# gsm.net
KiCad netlist of a schematic drawn in Altium Designer
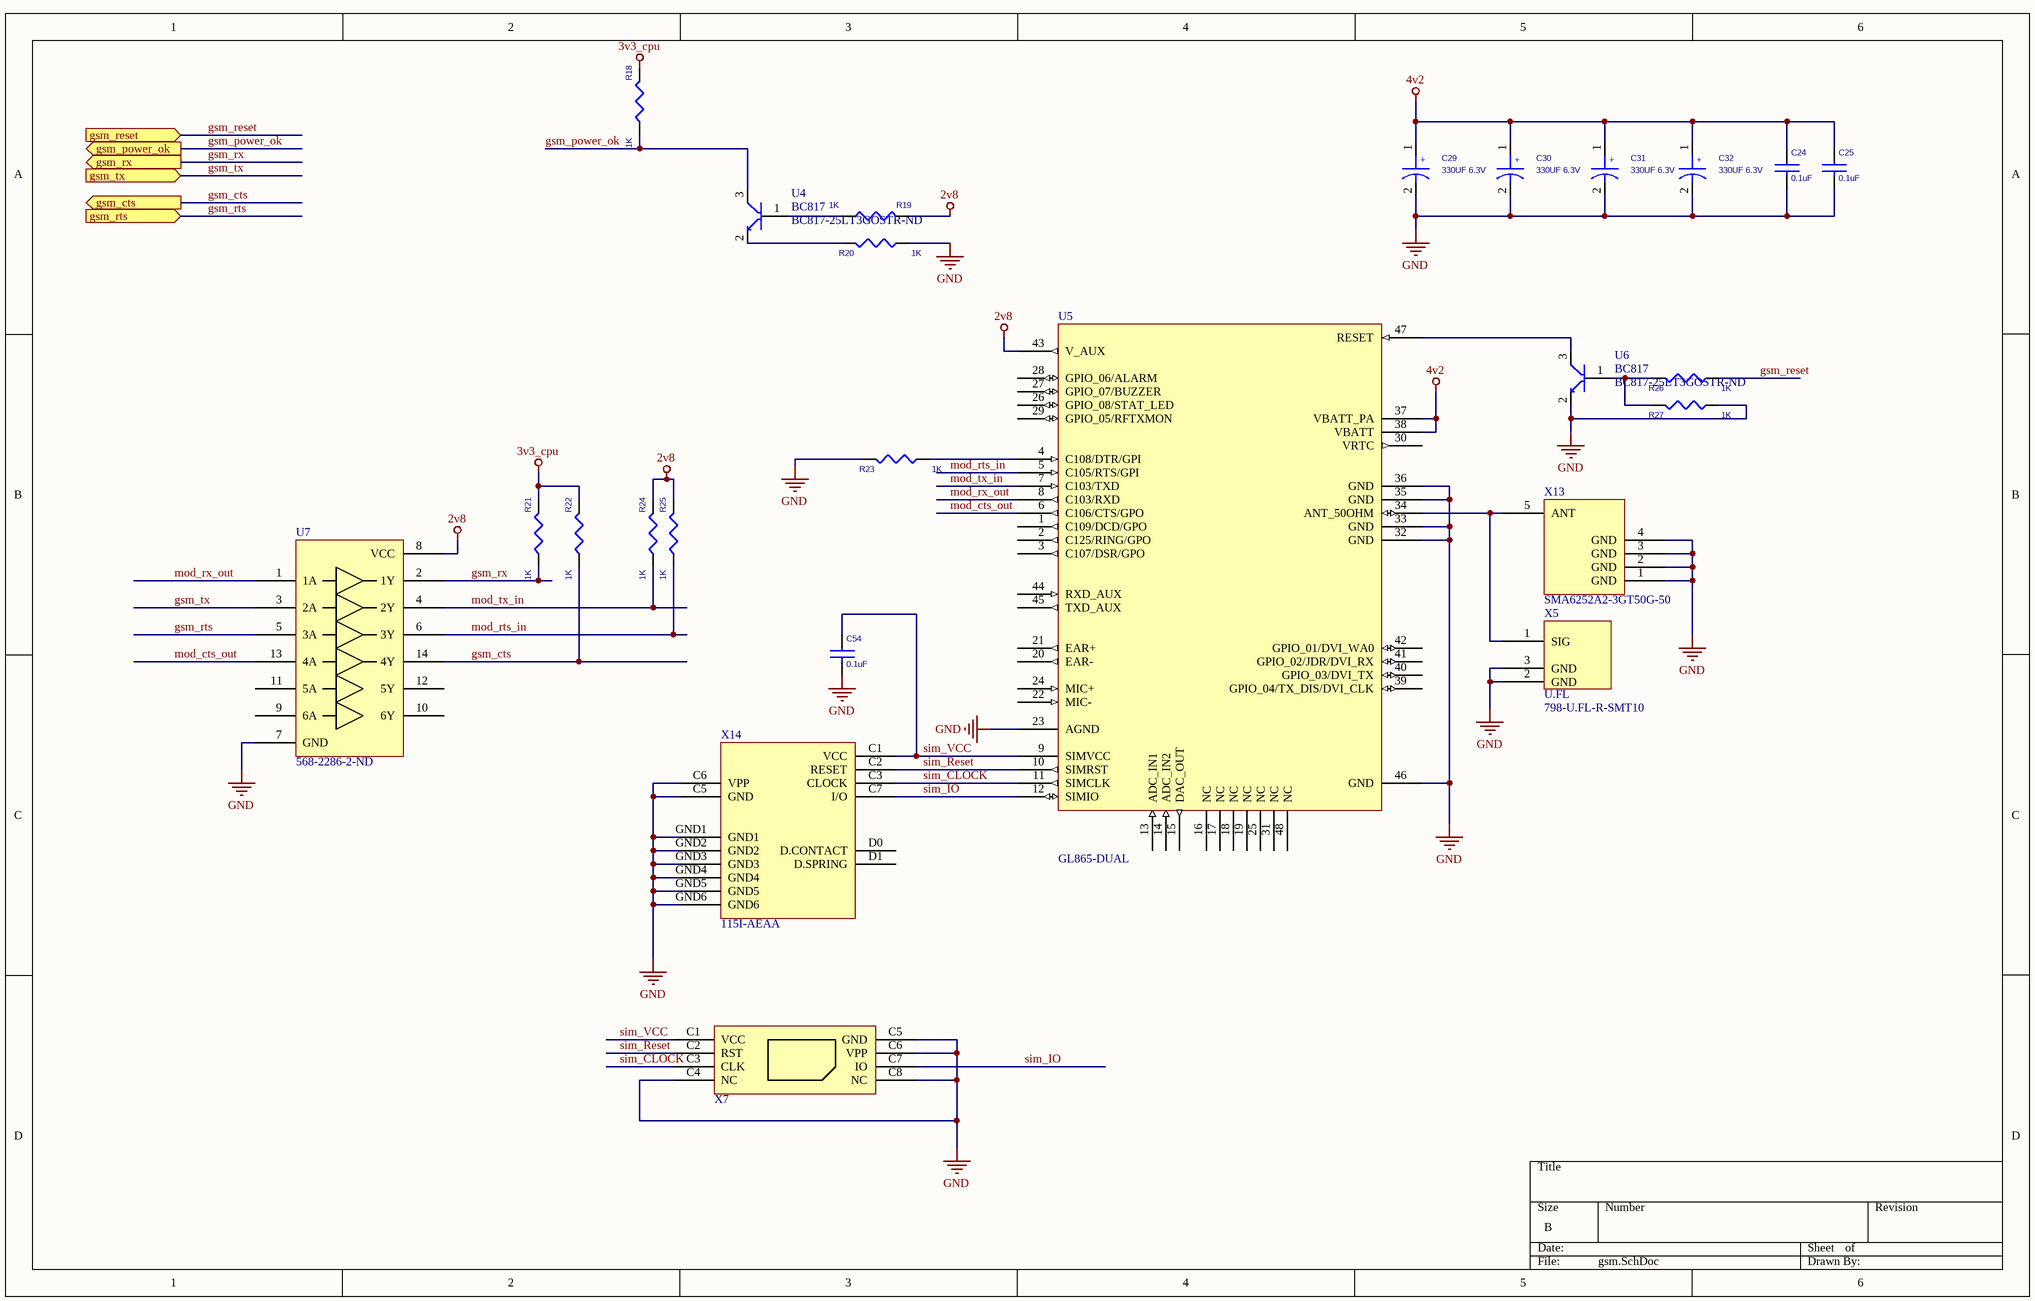
[diagram p0: gsm.SchDoc]

(export (version "E")
  (design (tool "Eeschema 10.0.6"))
  (components
    (comp (ref "C24")
      (value "0.1uF")
      (footprint "CAPC2012X09M")
      (description "CAP CER 0.1UF 25V 10% X7R 0805")
      (libsource (lib "Capacitors") (part "CAP_SMD_0.1UF_10%"))
    )
    (comp (ref "C25")
      (value "0.1uF")
      (footprint "CAPC2012X09M")
      (description "CAP CER 0.1UF 25V 10% X7R 0805")
      (libsource (lib "Capacitors") (part "CAP_SMD_0.1UF_10%"))
    )
    (comp (ref "C29")
      (value "330UF 6.3V")
      (footprint "CAPMP7143X31N")
      (description "CAP 330uF; 6.3V; Case: D")
      (libsource (lib "Capacitors") (part "CAP_SMD_330UF_10%"))
    )
    (comp (ref "C30")
      (value "330UF 6.3V")
      (footprint "CAPMP7143X31N")
      (description "CAP 330uF; 6.3V; Case: D")
      (libsource (lib "Capacitors") (part "CAP_SMD_330UF_10%"))
    )
    (comp (ref "C31")
      (value "330UF 6.3V")
      (footprint "CAPMP7143X31N")
      (description "CAP 330uF; 6.3V; Case: D")
      (libsource (lib "Capacitors") (part "CAP_SMD_330UF_10%"))
    )
    (comp (ref "C32")
      (value "330UF 6.3V")
      (footprint "CAPMP7143X31N")
      (description "CAP 330uF; 6.3V; Case: D")
      (libsource (lib "Capacitors") (part "CAP_SMD_330UF_10%"))
    )
    (comp (ref "C54")
      (value "0.1uF")
      (footprint "CAPC2012X09M")
      (description "CAP CER 0.1UF 25V 10% X7R 0805")
      (libsource (lib "Capacitors") (part "CAP_SMD_0.1UF_10%"))
    )
    (comp (ref "R18")
      (value "1K")
      (footprint "RESC2013X06M")
      (description "RES - 1K OHM, 5%, 1/8W, 0805 SMD")
      (libsource (lib "Resistors") (part "RES_SMD_1K_5%"))
    )
    (comp (ref "R19")
      (value "1K")
      (footprint "RESC2013X06M")
      (description "RES - 1K OHM, 5%, 1/8W, 0805 SMD")
      (libsource (lib "Resistors") (part "RES_SMD_1K_5%"))
    )
    (comp (ref "R20")
      (value "1K")
      (footprint "RESC2013X06M")
      (description "RES - 1K OHM, 5%, 1/8W, 0805 SMD")
      (libsource (lib "Resistors") (part "RES_SMD_1K_5%"))
    )
    (comp (ref "R21")
      (value "1K")
      (footprint "RESC2013X06M")
      (description "RES - 1K OHM, 5%, 1/8W, 0805 SMD")
      (libsource (lib "Resistors") (part "RES_SMD_1K_5%"))
    )
    (comp (ref "R22")
      (value "1K")
      (footprint "RESC2013X06M")
      (description "RES - 1K OHM, 5%, 1/8W, 0805 SMD")
      (libsource (lib "Resistors") (part "RES_SMD_1K_5%"))
    )
    (comp (ref "R23")
      (value "1K")
      (footprint "RESC2013X06M")
      (description "RES - 1K OHM, 5%, 1/8W, 0805 SMD")
      (libsource (lib "Resistors") (part "RES_SMD_1K_5%"))
    )
    (comp (ref "R24")
      (value "1K")
      (footprint "RESC2013X06M")
      (description "RES - 1K OHM, 5%, 1/8W, 0805 SMD")
      (libsource (lib "Resistors") (part "RES_SMD_1K_5%"))
    )
    (comp (ref "R25")
      (value "1K")
      (footprint "RESC2013X06M")
      (description "RES - 1K OHM, 5%, 1/8W, 0805 SMD")
      (libsource (lib "Resistors") (part "RES_SMD_1K_5%"))
    )
    (comp (ref "R26")
      (value "1K")
      (footprint "RESC2013X06M")
      (description "RES - 1K OHM, 5%, 1/8W, 0805 SMD")
      (libsource (lib "Resistors") (part "RES_SMD_1K_5%"))
    )
    (comp (ref "R27")
      (value "1K")
      (footprint "RESC2013X06M")
      (description "RES - 1K OHM, 5%, 1/8W, 0805 SMD")
      (libsource (lib "Resistors") (part "RES_SMD_1K_5%"))
    )
    (comp (ref "U4")
      (value "BC817")
      (footprint "SOT95P237X111-3N_SOT-23")
      (fields (field (name "SUPPLIER PART NUMBER 1") "BC817-25LT3GOSTR-ND"))
      (libsource (lib "TruthEar") (part "BC817"))
    )
    (comp (ref "U5")
      (value "GL865-DUAL")
      (footprint "GL865_FOOT")
      (libsource (lib "TruthEar") (part "GL865-DUAL"))
    )
    (comp (ref "U6")
      (value "BC817")
      (footprint "SOT95P237X111-3N_SOT-23")
      (fields (field (name "SUPPLIER PART NUMBER 1") "BC817-25LT3GOSTR-ND"))
      (libsource (lib "TruthEar") (part "BC817"))
    )
    (comp (ref "U7")
      (value "74LVC07A")
      (footprint "TSOP127P600X145-14N")
      (fields (field (name "SUPPLIER PART NUMBER 1") "568-2286-2-ND"))
      (libsource (lib "TruthEar") (part "74LVC07A"))
    )
    (comp (ref "X5")
      (value "U.FL")
      (footprint "U.FL")
      (fields (field (name "SUPPLIER PART NUMBER 1") "798-U.FL-R-SMT10"))
      (libsource (lib "Connectors") (part "U.FL"))
    )
    (comp (ref "X7")
      (value "MOLEX")
      (footprint "MOLEX-91228-001")
      (libsource (lib "Connectors") (part "MOLEX_SIM"))
    )
    (comp (ref "X13")
      (value "SMA6252A2-3GT50G-50")
      (footprint "SMA6252A2-3GT50G-50")
      (libsource (lib "Connectors") (part "SMA_CONN"))
    )
    (comp (ref "X14")
      (value "115I-AEAA")
      (footprint "115I-AEAA")
      (libsource (lib "Connectors") (part "SIM_CARD_115I-AEAA"))
    )
  )
  (nets
    (net (code "1") (name "/gsm_cts") (class "Default")
      (node (ref "R22") (pin "1") (pinfunction "1_1") (pintype "passive"))
      (node (ref "U7") (pin "14") (pinfunction "4Y_14") (pintype "power_in"))
    )
    (net (code "2") (name "/gsm_power_ok") (class "Default")
      (node (ref "R18") (pin "1") (pinfunction "1_1") (pintype "passive"))
      (node (ref "U4") (pin "3") (pinfunction "C_3") (pintype "passive"))
    )
    (net (code "3") (name "/gsm_reset") (class "Default")
      (node (ref "R26") (pin "1") (pinfunction "1_1") (pintype "passive"))
    )
    (net (code "4") (name "/gsm_rts") (class "Default")
      (node (ref "U7") (pin "5") (pinfunction "3A_5") (pintype "power_in"))
    )
    (net (code "5") (name "/gsm_rx") (class "Default")
      (node (ref "R21") (pin "1") (pinfunction "1_1") (pintype "passive"))
      (node (ref "U7") (pin "2") (pinfunction "1Y_2") (pintype "power_in"))
    )
    (net (code "6") (name "/gsm_tx") (class "Default")
      (node (ref "U7") (pin "3") (pinfunction "2A_3") (pintype "power_in"))
    )
    (net (code "7") (name "/mod_cts_out") (class "Default")
      (node (ref "U5") (pin "6") (pinfunction "C106/CTS/GPO_6") (pintype "output"))
      (node (ref "U7") (pin "13") (pinfunction "4A_13") (pintype "power_in"))
    )
    (net (code "8") (name "/mod_rts_in") (class "Default")
      (node (ref "R25") (pin "1") (pinfunction "1_1") (pintype "passive"))
      (node (ref "U5") (pin "5") (pinfunction "C105/RTS/GPI_5") (pintype "input"))
      (node (ref "U7") (pin "6") (pinfunction "3Y_6") (pintype "power_in"))
    )
    (net (code "9") (name "/mod_rx_out") (class "Default")
      (node (ref "U5") (pin "8") (pinfunction "C103/RXD_8") (pintype "output"))
      (node (ref "U7") (pin "1") (pinfunction "1A_1") (pintype "power_in"))
    )
    (net (code "10") (name "/mod_tx_in") (class "Default")
      (node (ref "R24") (pin "1") (pinfunction "1_1") (pintype "passive"))
      (node (ref "U5") (pin "7") (pinfunction "C103/TXD_7") (pintype "input"))
      (node (ref "U7") (pin "4") (pinfunction "2Y_4") (pintype "power_in"))
    )
    (net (code "11") (name "/sim_CLOCK") (class "Default")
      (node (ref "U5") (pin "11") (pinfunction "SIMCLK_11") (pintype "output"))
      (node (ref "X14") (pin "C3") (pinfunction "CLOCK_C3") (pintype "passive"))
      (node (ref "X7") (pin "C3") (pinfunction "CLK_C3") (pintype "power_in"))
    )
    (net (code "12") (name "/sim_IO") (class "Default")
      (node (ref "U5") (pin "12") (pinfunction "SIMIO_12") (pintype "bidirectional"))
      (node (ref "X14") (pin "C7") (pinfunction "I/O_C7") (pintype "passive"))
      (node (ref "X7") (pin "C7") (pinfunction "IO_C7") (pintype "power_in"))
    )
    (net (code "13") (name "/sim_Reset") (class "Default")
      (node (ref "U5") (pin "10") (pinfunction "SIMRST_10") (pintype "output"))
      (node (ref "X14") (pin "C2") (pinfunction "RESET_C2") (pintype "passive"))
      (node (ref "X7") (pin "C2") (pinfunction "RST_C2") (pintype "power_in"))
    )
    (net (code "14") (name "/sim_VCC") (class "Default")
      (node (ref "C54") (pin "1") (pinfunction "1_1") (pintype "passive"))
      (node (ref "U5") (pin "9") (pinfunction "SIMVCC_9") (pintype "passive"))
      (node (ref "X14") (pin "C1") (pinfunction "VCC_C1") (pintype "passive"))
      (node (ref "X7") (pin "C1") (pinfunction "VCC_C1") (pintype "power_in"))
    )
    (net (code "15") (name "2v8") (class "Default")
      (node (ref "R19") (pin "2") (pinfunction "2_2") (pintype "passive"))
      (node (ref "R24") (pin "2") (pinfunction "2_2") (pintype "passive"))
      (node (ref "R25") (pin "2") (pinfunction "2_2") (pintype "passive"))
      (node (ref "U5") (pin "43") (pinfunction "V_AUX_43") (pintype "output"))
      (node (ref "U7") (pin "8") (pinfunction "VCC_8") (pintype "power_in"))
    )
    (net (code "16") (name "3v3_cpu") (class "Default")
      (node (ref "R18") (pin "2") (pinfunction "2_2") (pintype "passive"))
      (node (ref "R21") (pin "2") (pinfunction "2_2") (pintype "passive"))
      (node (ref "R22") (pin "2") (pinfunction "2_2") (pintype "passive"))
    )
    (net (code "17") (name "4v2") (class "Default")
      (node (ref "C24") (pin "1") (pinfunction "1_1") (pintype "passive"))
      (node (ref "C25") (pin "1") (pinfunction "1_1") (pintype "passive"))
      (node (ref "C29") (pin "1") (pinfunction "1_1") (pintype "passive"))
      (node (ref "C30") (pin "1") (pinfunction "1_1") (pintype "passive"))
      (node (ref "C31") (pin "1") (pinfunction "1_1") (pintype "passive"))
      (node (ref "C32") (pin "1") (pinfunction "1_1") (pintype "passive"))
      (node (ref "U5") (pin "37") (pinfunction "VBATT_PA_37") (pintype "passive"))
      (node (ref "U5") (pin "38") (pinfunction "VBATT_38") (pintype "passive"))
    )
    (net (code "18") (name "GND") (class "Default")
      (node (ref "C24") (pin "2") (pinfunction "2_2") (pintype "passive"))
      (node (ref "C25") (pin "2") (pinfunction "2_2") (pintype "passive"))
      (node (ref "C29") (pin "2") (pinfunction "2_2") (pintype "passive"))
      (node (ref "C30") (pin "2") (pinfunction "2_2") (pintype "passive"))
      (node (ref "C31") (pin "2") (pinfunction "2_2") (pintype "passive"))
      (node (ref "C32") (pin "2") (pinfunction "2_2") (pintype "passive"))
      (node (ref "C54") (pin "2") (pinfunction "2_2") (pintype "passive"))
      (node (ref "R20") (pin "1") (pinfunction "1_1") (pintype "passive"))
      (node (ref "R23") (pin "2") (pinfunction "2_2") (pintype "passive"))
      (node (ref "R27") (pin "1") (pinfunction "1_1") (pintype "passive"))
      (node (ref "U5") (pin "23") (pinfunction "AGND_23") (pintype "passive"))
      (node (ref "U5") (pin "32") (pinfunction "GND_32") (pintype "passive"))
      (node (ref "U5") (pin "33") (pinfunction "GND_33") (pintype "passive"))
      (node (ref "U5") (pin "35") (pinfunction "GND_35") (pintype "passive"))
      (node (ref "U5") (pin "36") (pinfunction "GND_36") (pintype "passive"))
      (node (ref "U5") (pin "46") (pinfunction "GND_46") (pintype "passive"))
      (node (ref "U6") (pin "2") (pinfunction "E_2") (pintype "passive"))
      (node (ref "U7") (pin "7") (pinfunction "GND_7") (pintype "power_in"))
      (node (ref "X13") (pin "1") (pinfunction "GND_1") (pintype "passive"))
      (node (ref "X13") (pin "2") (pinfunction "GND_2") (pintype "passive"))
      (node (ref "X13") (pin "3") (pinfunction "GND_3") (pintype "passive"))
      (node (ref "X13") (pin "4") (pinfunction "GND_4") (pintype "passive"))
      (node (ref "X14") (pin "C5") (pinfunction "GND_C5") (pintype "passive"))
      (node (ref "X14") (pin "C6") (pinfunction "VPP_C6") (pintype "passive"))
      (node (ref "X14") (pin "GND1") (pinfunction "GND1_GND1") (pintype "passive"))
      (node (ref "X14") (pin "GND2") (pinfunction "GND2_GND2") (pintype "passive"))
      (node (ref "X14") (pin "GND3") (pinfunction "GND3_GND3") (pintype "passive"))
      (node (ref "X14") (pin "GND4") (pinfunction "GND4_GND4") (pintype "passive"))
      (node (ref "X14") (pin "GND5") (pinfunction "GND5_GND5") (pintype "passive"))
      (node (ref "X14") (pin "GND6") (pinfunction "GND6_GND6") (pintype "passive"))
      (node (ref "X5") (pin "2") (pinfunction "GND_2") (pintype "passive"))
      (node (ref "X5") (pin "3") (pinfunction "GND_3") (pintype "passive"))
      (node (ref "X7") (pin "C4") (pinfunction "NC_C4") (pintype "power_in"))
      (node (ref "X7") (pin "C5") (pinfunction "GND_C5") (pintype "power_in"))
      (node (ref "X7") (pin "C6") (pinfunction "VPP_C6") (pintype "power_in"))
      (node (ref "X7") (pin "C8") (pinfunction "NC_C8") (pintype "power_in"))
    )
    (net (code "19") (name "Net-(U4-B)") (class "Default")
      (node (ref "R19") (pin "1") (pinfunction "1_1") (pintype "passive"))
      (node (ref "U4") (pin "1") (pinfunction "B_1") (pintype "passive"))
    )
    (net (code "20") (name "Net-(U4-E)") (class "Default")
      (node (ref "R20") (pin "2") (pinfunction "2_2") (pintype "passive"))
      (node (ref "U4") (pin "2") (pinfunction "E_2") (pintype "passive"))
    )
    (net (code "21") (name "Net-(U5-ANT_50OHM)") (class "Default")
      (node (ref "U5") (pin "34") (pinfunction "ANT_50OHM_34") (pintype "bidirectional"))
      (node (ref "X13") (pin "5") (pinfunction "ANT_5") (pintype "passive"))
      (node (ref "X5") (pin "1") (pinfunction "SIG_1") (pintype "passive"))
    )
    (net (code "22") (name "Net-(U5-C108{slash}DTR{slash}GPI)") (class "Default")
      (node (ref "R23") (pin "1") (pinfunction "1_1") (pintype "passive"))
      (node (ref "U5") (pin "4") (pinfunction "C108/DTR/GPI_4") (pintype "input"))
    )
    (net (code "23") (name "Net-(U5-RESET)") (class "Default")
      (node (ref "U5") (pin "47") (pinfunction "RESET_47") (pintype "input"))
      (node (ref "U6") (pin "3") (pinfunction "C_3") (pintype "passive"))
    )
    (net (code "24") (name "Net-(U6-B)") (class "Default")
      (node (ref "R26") (pin "2") (pinfunction "2_2") (pintype "passive"))
      (node (ref "R27") (pin "2") (pinfunction "2_2") (pintype "passive"))
      (node (ref "U6") (pin "1") (pinfunction "B_1") (pintype "passive"))
    )
    (net (code "25") (name "unconnected-(U5-ADC_IN1-Pad13)") (class "Default")
      (node (ref "U5") (pin "13") (pinfunction "ADC_IN1_13") (pintype "input"))
    )
    (net (code "26") (name "unconnected-(U5-ADC_IN2-Pad14)") (class "Default")
      (node (ref "U5") (pin "14") (pinfunction "ADC_IN2_14") (pintype "input"))
    )
    (net (code "27") (name "unconnected-(U5-C107{slash}DSR{slash}GPO-Pad3)") (class "Default")
      (node (ref "U5") (pin "3") (pinfunction "C107/DSR/GPO_3") (pintype "output"))
    )
    (net (code "28") (name "unconnected-(U5-C109{slash}DCD{slash}GPO-Pad1)") (class "Default")
      (node (ref "U5") (pin "1") (pinfunction "C109/DCD/GPO_1") (pintype "output"))
    )
    (net (code "29") (name "unconnected-(U5-C125{slash}RING{slash}GPO-Pad2)") (class "Default")
      (node (ref "U5") (pin "2") (pinfunction "C125/RING/GPO_2") (pintype "output"))
    )
    (net (code "30") (name "unconnected-(U5-DAC_OUT-Pad15)") (class "Default")
      (node (ref "U5") (pin "15") (pinfunction "DAC_OUT_15") (pintype "output"))
    )
    (net (code "31") (name "unconnected-(U5-EAR+-Pad21)") (class "Default")
      (node (ref "U5") (pin "21") (pinfunction "EAR+_21") (pintype "output"))
    )
    (net (code "32") (name "unconnected-(U5-EAR--Pad20)") (class "Default")
      (node (ref "U5") (pin "20") (pinfunction "EAR-_20") (pintype "output"))
    )
    (net (code "33") (name "unconnected-(U5-GPIO_01{slash}DVI_WA0-Pad42)") (class "Default")
      (node (ref "U5") (pin "42") (pinfunction "GPIO_01/DVI_WA0_42") (pintype "bidirectional"))
    )
    (net (code "34") (name "unconnected-(U5-GPIO_02{slash}JDR{slash}DVI_RX-Pad41)") (class "Default")
      (node (ref "U5") (pin "41") (pinfunction "GPIO_02/JDR/DVI_RX_41") (pintype "bidirectional"))
    )
    (net (code "35") (name "unconnected-(U5-GPIO_03{slash}DVI_TX-Pad40)") (class "Default")
      (node (ref "U5") (pin "40") (pinfunction "GPIO_03/DVI_TX_40") (pintype "bidirectional"))
    )
    (net (code "36") (name "unconnected-(U5-GPIO_04{slash}TX_DIS{slash}DVI_CLK-Pad39)") (class "Default")
      (node (ref "U5") (pin "39") (pinfunction "GPIO_04/TX_DIS/DVI_CLK_39") (pintype "bidirectional"))
    )
    (net (code "37") (name "unconnected-(U5-GPIO_05{slash}RFTXMON-Pad29)") (class "Default")
      (node (ref "U5") (pin "29") (pinfunction "GPIO_05/RFTXMON_29") (pintype "bidirectional"))
    )
    (net (code "38") (name "unconnected-(U5-GPIO_06{slash}ALARM-Pad28)") (class "Default")
      (node (ref "U5") (pin "28") (pinfunction "GPIO_06/ALARM_28") (pintype "bidirectional"))
    )
    (net (code "39") (name "unconnected-(U5-GPIO_07{slash}BUZZER-Pad27)") (class "Default")
      (node (ref "U5") (pin "27") (pinfunction "GPIO_07/BUZZER_27") (pintype "bidirectional"))
    )
    (net (code "40") (name "unconnected-(U5-GPIO_08{slash}STAT_LED-Pad26)") (class "Default")
      (node (ref "U5") (pin "26") (pinfunction "GPIO_08/STAT_LED_26") (pintype "bidirectional"))
    )
    (net (code "41") (name "unconnected-(U5-MIC+-Pad24)") (class "Default")
      (node (ref "U5") (pin "24") (pinfunction "MIC+_24") (pintype "input"))
    )
    (net (code "42") (name "unconnected-(U5-MIC--Pad22)") (class "Default")
      (node (ref "U5") (pin "22") (pinfunction "MIC-_22") (pintype "input"))
    )
    (net (code "43") (name "unconnected-(U5-NC-Pad16)") (class "Default")
      (node (ref "U5") (pin "16") (pinfunction "NC_16") (pintype "passive"))
    )
    (net (code "44") (name "unconnected-(U5-NC-Pad17)") (class "Default")
      (node (ref "U5") (pin "17") (pinfunction "NC_17") (pintype "passive"))
    )
    (net (code "45") (name "unconnected-(U5-NC-Pad18)") (class "Default")
      (node (ref "U5") (pin "18") (pinfunction "NC_18") (pintype "passive"))
    )
    (net (code "46") (name "unconnected-(U5-NC-Pad19)") (class "Default")
      (node (ref "U5") (pin "19") (pinfunction "NC_19") (pintype "passive"))
    )
    (net (code "47") (name "unconnected-(U5-NC-Pad25)") (class "Default")
      (node (ref "U5") (pin "25") (pinfunction "NC_25") (pintype "passive"))
    )
    (net (code "48") (name "unconnected-(U5-NC-Pad31)") (class "Default")
      (node (ref "U5") (pin "31") (pinfunction "NC_31") (pintype "passive"))
    )
    (net (code "49") (name "unconnected-(U5-NC-Pad48)") (class "Default")
      (node (ref "U5") (pin "48") (pinfunction "NC_48") (pintype "passive"))
    )
    (net (code "50") (name "unconnected-(U5-RXD_AUX-Pad44)") (class "Default")
      (node (ref "U5") (pin "44") (pinfunction "RXD_AUX_44") (pintype "input"))
    )
    (net (code "51") (name "unconnected-(U5-TXD_AUX-Pad45)") (class "Default")
      (node (ref "U5") (pin "45") (pinfunction "TXD_AUX_45") (pintype "output"))
    )
    (net (code "52") (name "unconnected-(U5-VRTC-Pad30)") (class "Default")
      (node (ref "U5") (pin "30") (pinfunction "VRTC_30") (pintype "output"))
    )
    (net (code "53") (name "unconnected-(U7-5A-Pad11)") (class "Default")
      (node (ref "U7") (pin "11") (pinfunction "5A_11") (pintype "power_in"))
    )
    (net (code "54") (name "unconnected-(U7-5Y-Pad12)") (class "Default")
      (node (ref "U7") (pin "12") (pinfunction "5Y_12") (pintype "power_in"))
    )
    (net (code "55") (name "unconnected-(U7-6A-Pad9)") (class "Default")
      (node (ref "U7") (pin "9") (pinfunction "6A_9") (pintype "power_in"))
    )
    (net (code "56") (name "unconnected-(U7-6Y-Pad10)") (class "Default")
      (node (ref "U7") (pin "10") (pinfunction "6Y_10") (pintype "power_in"))
    )
    (net (code "57") (name "unconnected-(X14-D.CONTACT-PadD0)") (class "Default")
      (node (ref "X14") (pin "D0") (pinfunction "D.CONTACT_D0") (pintype "passive"))
    )
    (net (code "58") (name "unconnected-(X14-D.SPRING-PadD1)") (class "Default")
      (node (ref "X14") (pin "D1") (pinfunction "D.SPRING_D1") (pintype "passive"))
    )
  )
)
